# Power.net
KiCad netlist of a schematic drawn in Altium Designer
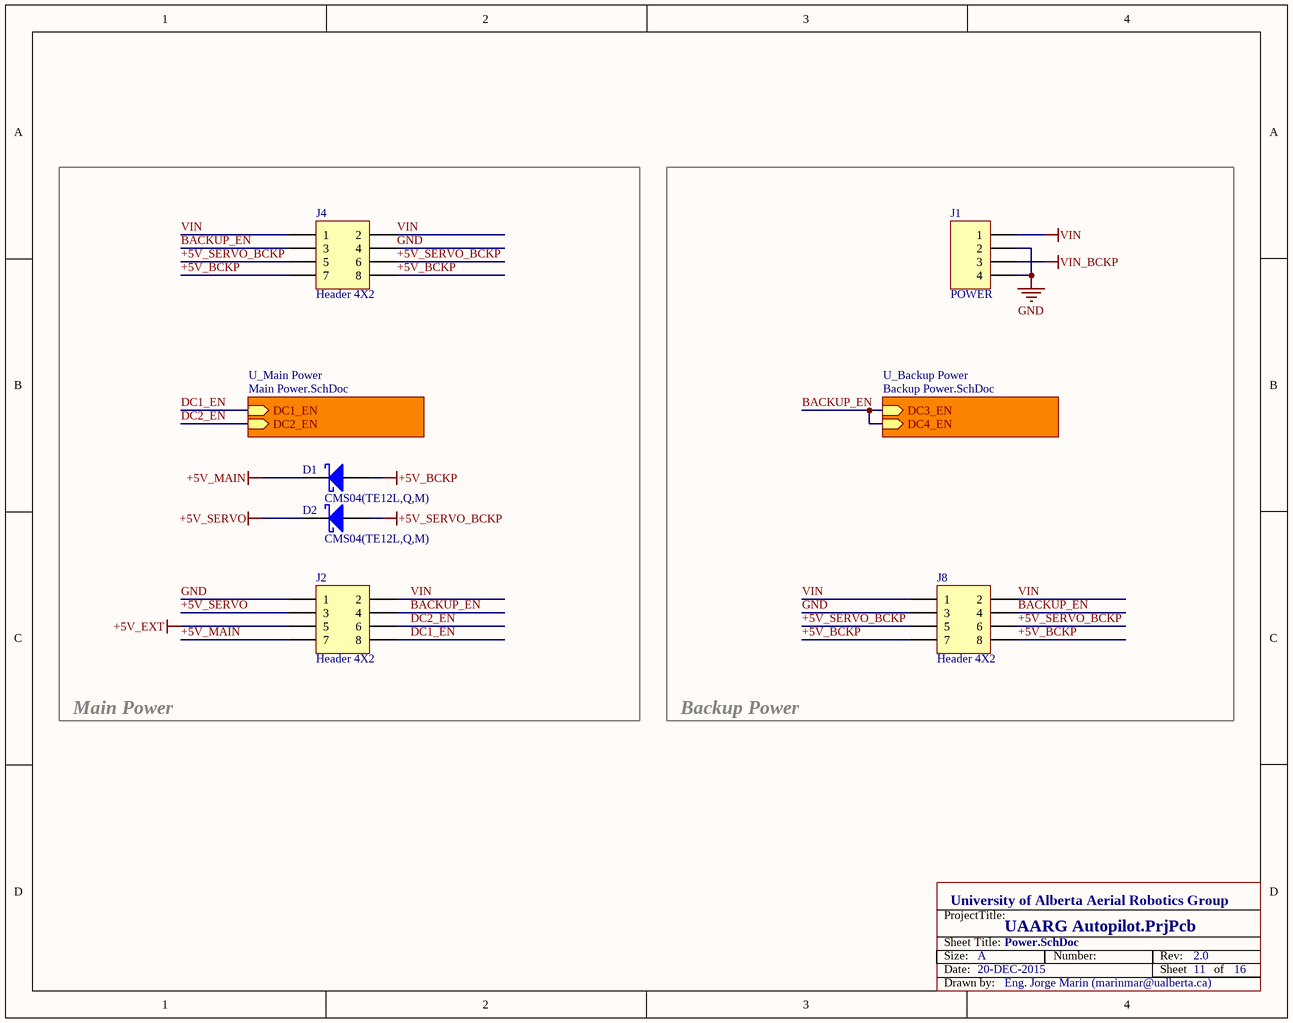
[diagram p0: Power.SchDoc]

(export (version "E")
  (design (tool "Eeschema 10.0.6"))
  (components
    (comp (ref "D1")
      (value "SCHOTTKY DIODE")
      (footprint "SOD-128")
      (description "Typical Schottky Diode")
      (fields
        (field (name "MANUFACTURER PART NUMBER") "CMS04(TE12L,Q,M)")
        (field (name "MANUFACTURER") "Toshiba Semiconductor and Storage")
      )
      (libsource (lib "UAARG Autopilot") (part "SCHOTTKY DIODE"))
    )
    (comp (ref "D2")
      (value "SCHOTTKY DIODE")
      (footprint "SOD-128")
      (description "Typical Schottky Diode")
      (fields
        (field (name "MANUFACTURER PART NUMBER") "CMS04(TE12L,Q,M)")
        (field (name "MANUFACTURER") "Toshiba Semiconductor and Storage")
      )
      (libsource (lib "UAARG Autopilot") (part "SCHOTTKY DIODE"))
    )
    (comp (ref "J1")
      (value "POWER")
      (footprint "1X04_v2")
      (description "Header, 4-Pin")
      (libsource (lib "Miscellaneous Connectors") (part "Header 4"))
    )
    (comp (ref "J2")
      (value "Header 4X2")
      (footprint "2X04")
      (description "Header, 4-Pin, Dual row")
      (libsource (lib "Miscellaneous Connectors") (part "Header 4X2"))
    )
    (comp (ref "J4")
      (value "Header 4X2")
      (footprint "2X04")
      (description "Header, 4-Pin, Dual row")
      (libsource (lib "Miscellaneous Connectors") (part "Header 4X2"))
    )
    (comp (ref "J8")
      (value "Header 4X2")
      (footprint "2X04")
      (description "Header, 4-Pin, Dual row")
      (libsource (lib "Miscellaneous Connectors") (part "Header 4X2"))
    )
  )
  (nets
    (net (code "1") (name "+5V_BCKP") (class "Default")
      (node (ref "D1") (pin "1") (pinfunction "A_1") (pintype "passive"))
      (node (ref "J4") (pin "7") (pinfunction "7_7") (pintype "passive"))
      (node (ref "J4") (pin "8") (pinfunction "8_8") (pintype "passive"))
      (node (ref "J8") (pin "7") (pinfunction "7_7") (pintype "passive"))
      (node (ref "J8") (pin "8") (pinfunction "8_8") (pintype "passive"))
    )
    (net (code "2") (name "+5V_EXT") (class "Default")
      (node (ref "J2") (pin "5") (pinfunction "5_5") (pintype "passive"))
    )
    (net (code "3") (name "+5V_MAIN") (class "Default")
      (node (ref "D1") (pin "2") (pinfunction "K_2") (pintype "passive"))
      (node (ref "J2") (pin "7") (pinfunction "7_7") (pintype "passive"))
    )
    (net (code "4") (name "+5V_SERVO") (class "Default")
      (node (ref "D2") (pin "2") (pinfunction "K_2") (pintype "passive"))
      (node (ref "J2") (pin "3") (pinfunction "3_3") (pintype "passive"))
    )
    (net (code "5") (name "+5V_SERVO_BCKP") (class "Default")
      (node (ref "D2") (pin "1") (pinfunction "A_1") (pintype "passive"))
      (node (ref "J4") (pin "5") (pinfunction "5_5") (pintype "passive"))
      (node (ref "J4") (pin "6") (pinfunction "6_6") (pintype "passive"))
      (node (ref "J8") (pin "5") (pinfunction "5_5") (pintype "passive"))
      (node (ref "J8") (pin "6") (pinfunction "6_6") (pintype "passive"))
    )
    (net (code "6") (name "/BACKUP_EN") (class "Default")
      (node (ref "J2") (pin "4") (pinfunction "4_4") (pintype "passive"))
      (node (ref "J4") (pin "3") (pinfunction "3_3") (pintype "passive"))
      (node (ref "J8") (pin "4") (pinfunction "4_4") (pintype "passive"))
    )
    (net (code "7") (name "/DC1_EN") (class "Default")
      (node (ref "J2") (pin "8") (pinfunction "8_8") (pintype "passive"))
    )
    (net (code "8") (name "/DC2_EN") (class "Default")
      (node (ref "J2") (pin "6") (pinfunction "6_6") (pintype "passive"))
    )
    (net (code "9") (name "GND") (class "Default")
      (node (ref "J1") (pin "2") (pinfunction "2_2") (pintype "passive"))
      (node (ref "J1") (pin "4") (pinfunction "4_4") (pintype "passive"))
      (node (ref "J2") (pin "1") (pinfunction "1_1") (pintype "passive"))
      (node (ref "J4") (pin "4") (pinfunction "4_4") (pintype "passive"))
      (node (ref "J8") (pin "3") (pinfunction "3_3") (pintype "passive"))
    )
    (net (code "10") (name "VIN") (class "Default")
      (node (ref "J1") (pin "1") (pinfunction "1_1") (pintype "passive"))
      (node (ref "J2") (pin "2") (pinfunction "2_2") (pintype "passive"))
      (node (ref "J4") (pin "1") (pinfunction "1_1") (pintype "passive"))
      (node (ref "J4") (pin "2") (pinfunction "2_2") (pintype "passive"))
      (node (ref "J8") (pin "1") (pinfunction "1_1") (pintype "passive"))
      (node (ref "J8") (pin "2") (pinfunction "2_2") (pintype "passive"))
    )
    (net (code "11") (name "VIN_BCKP") (class "Default")
      (node (ref "J1") (pin "3") (pinfunction "3_3") (pintype "passive"))
    )
  )
)
